# Embedded_II_MAIN_BOARD.net
KiCad netlist of a schematic drawn in EAGLE
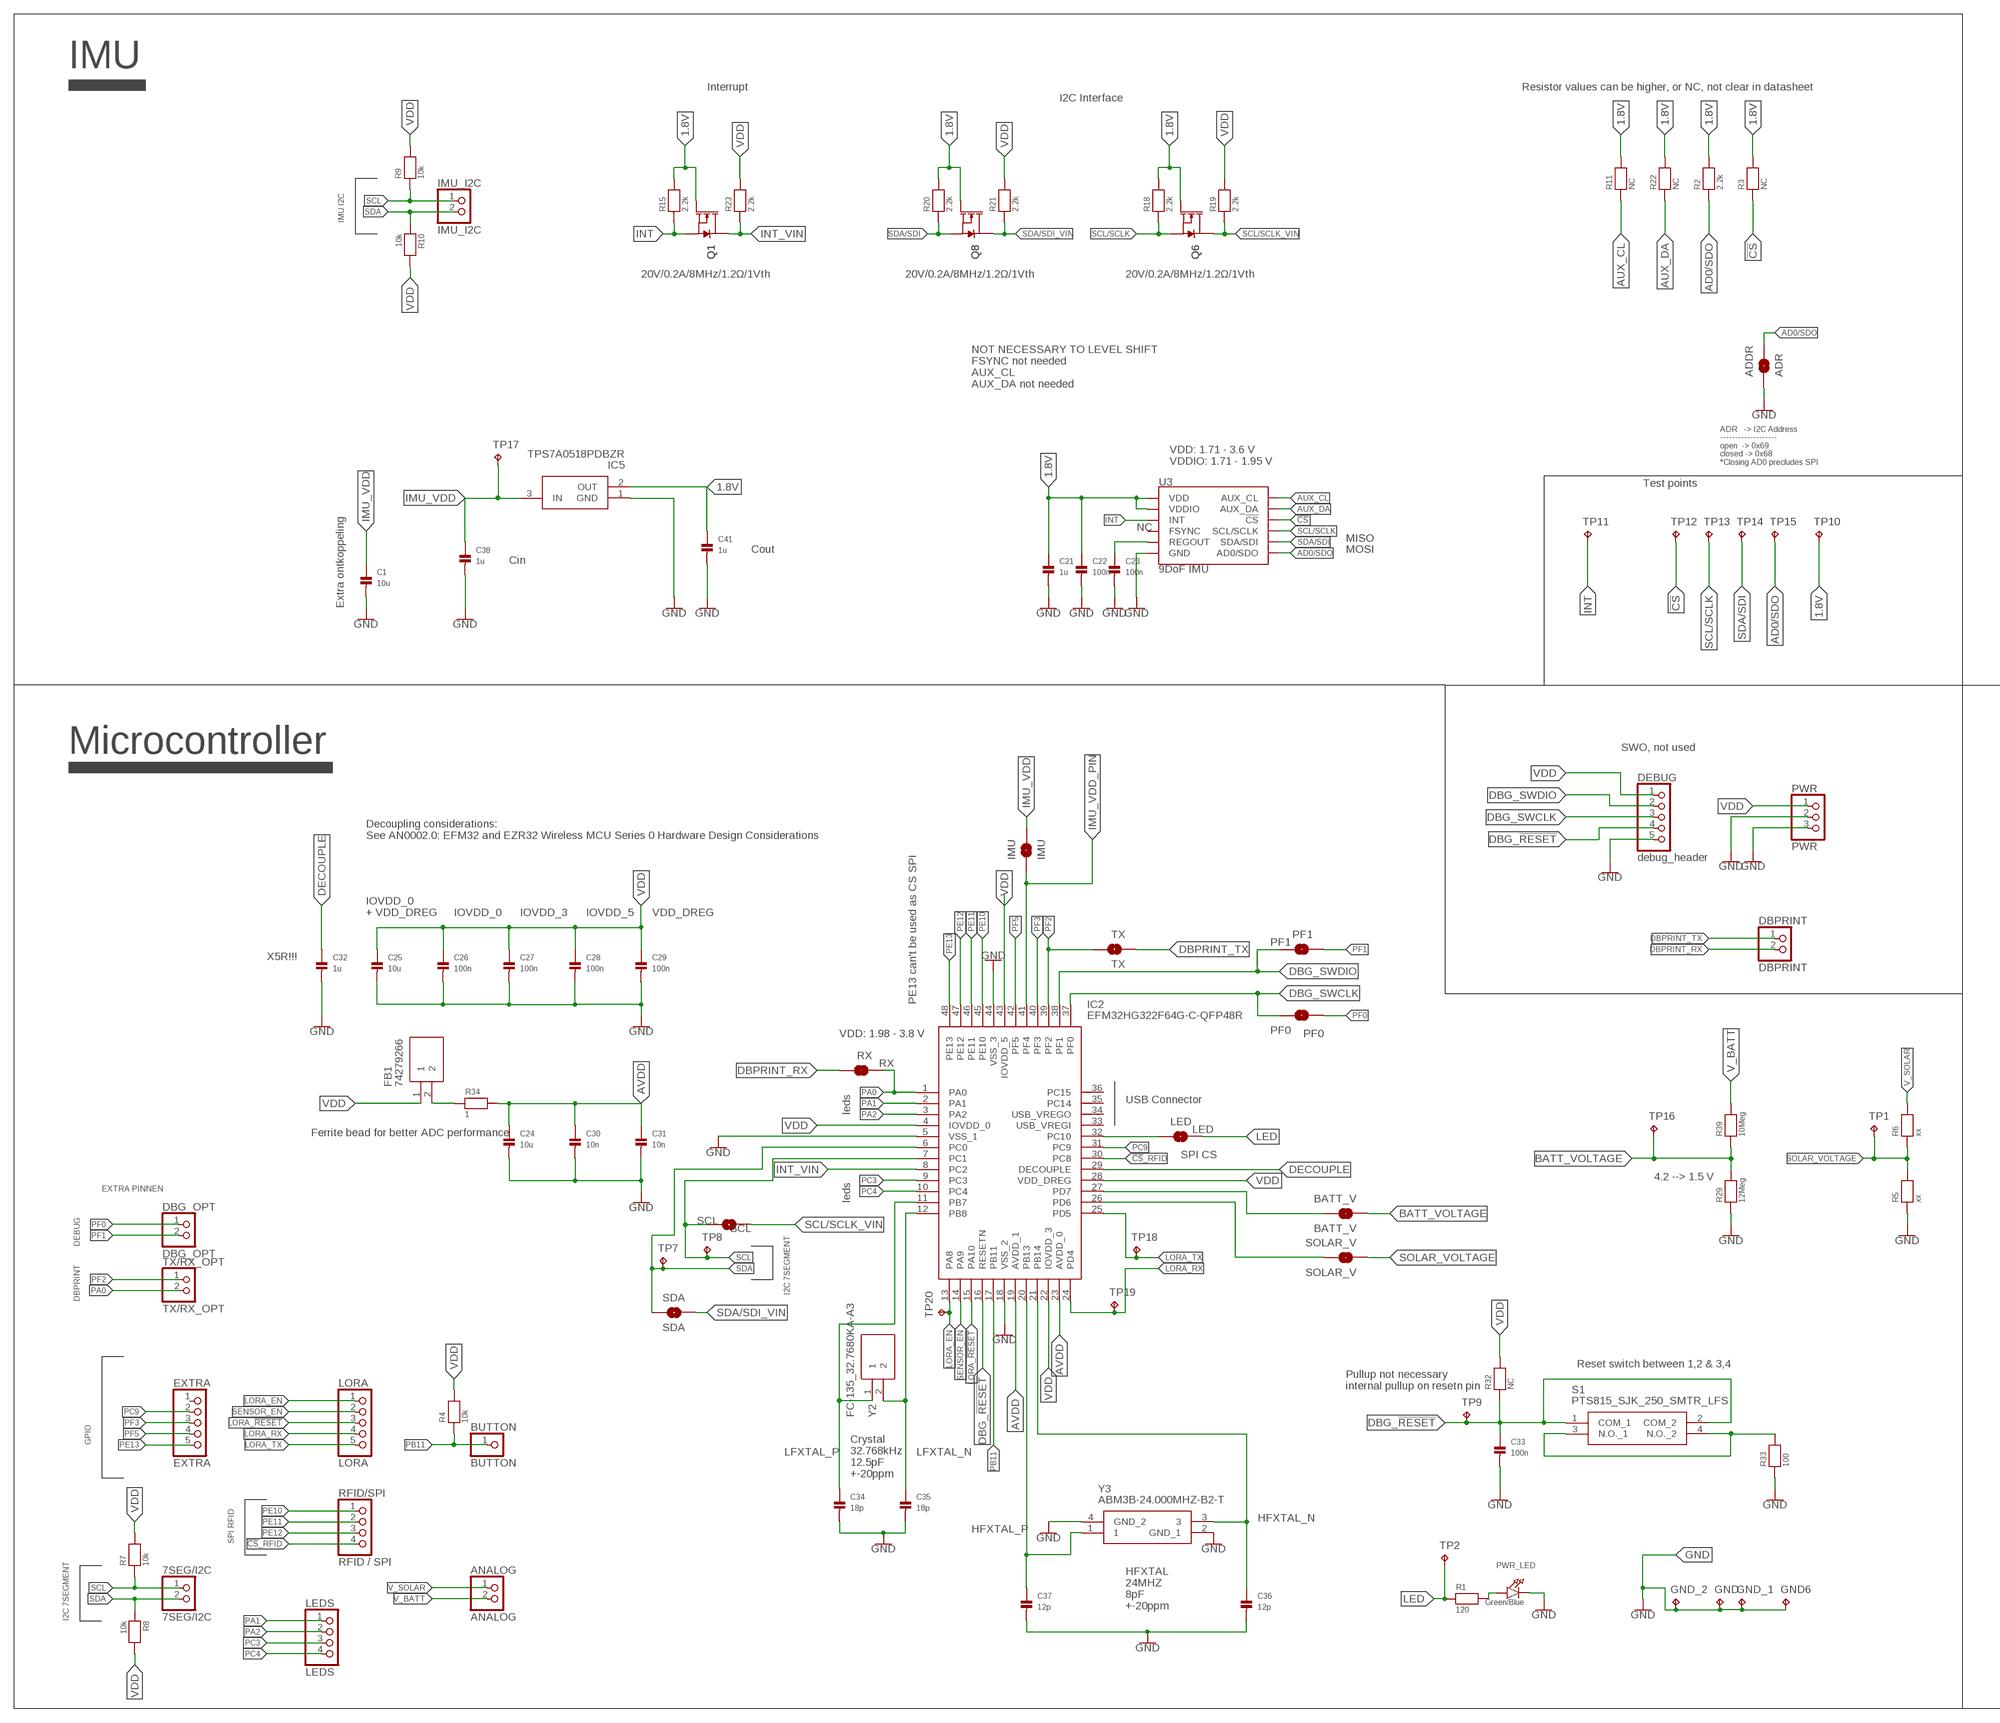
[diagram p0: schematic, sheet 1, part 1 of 2]
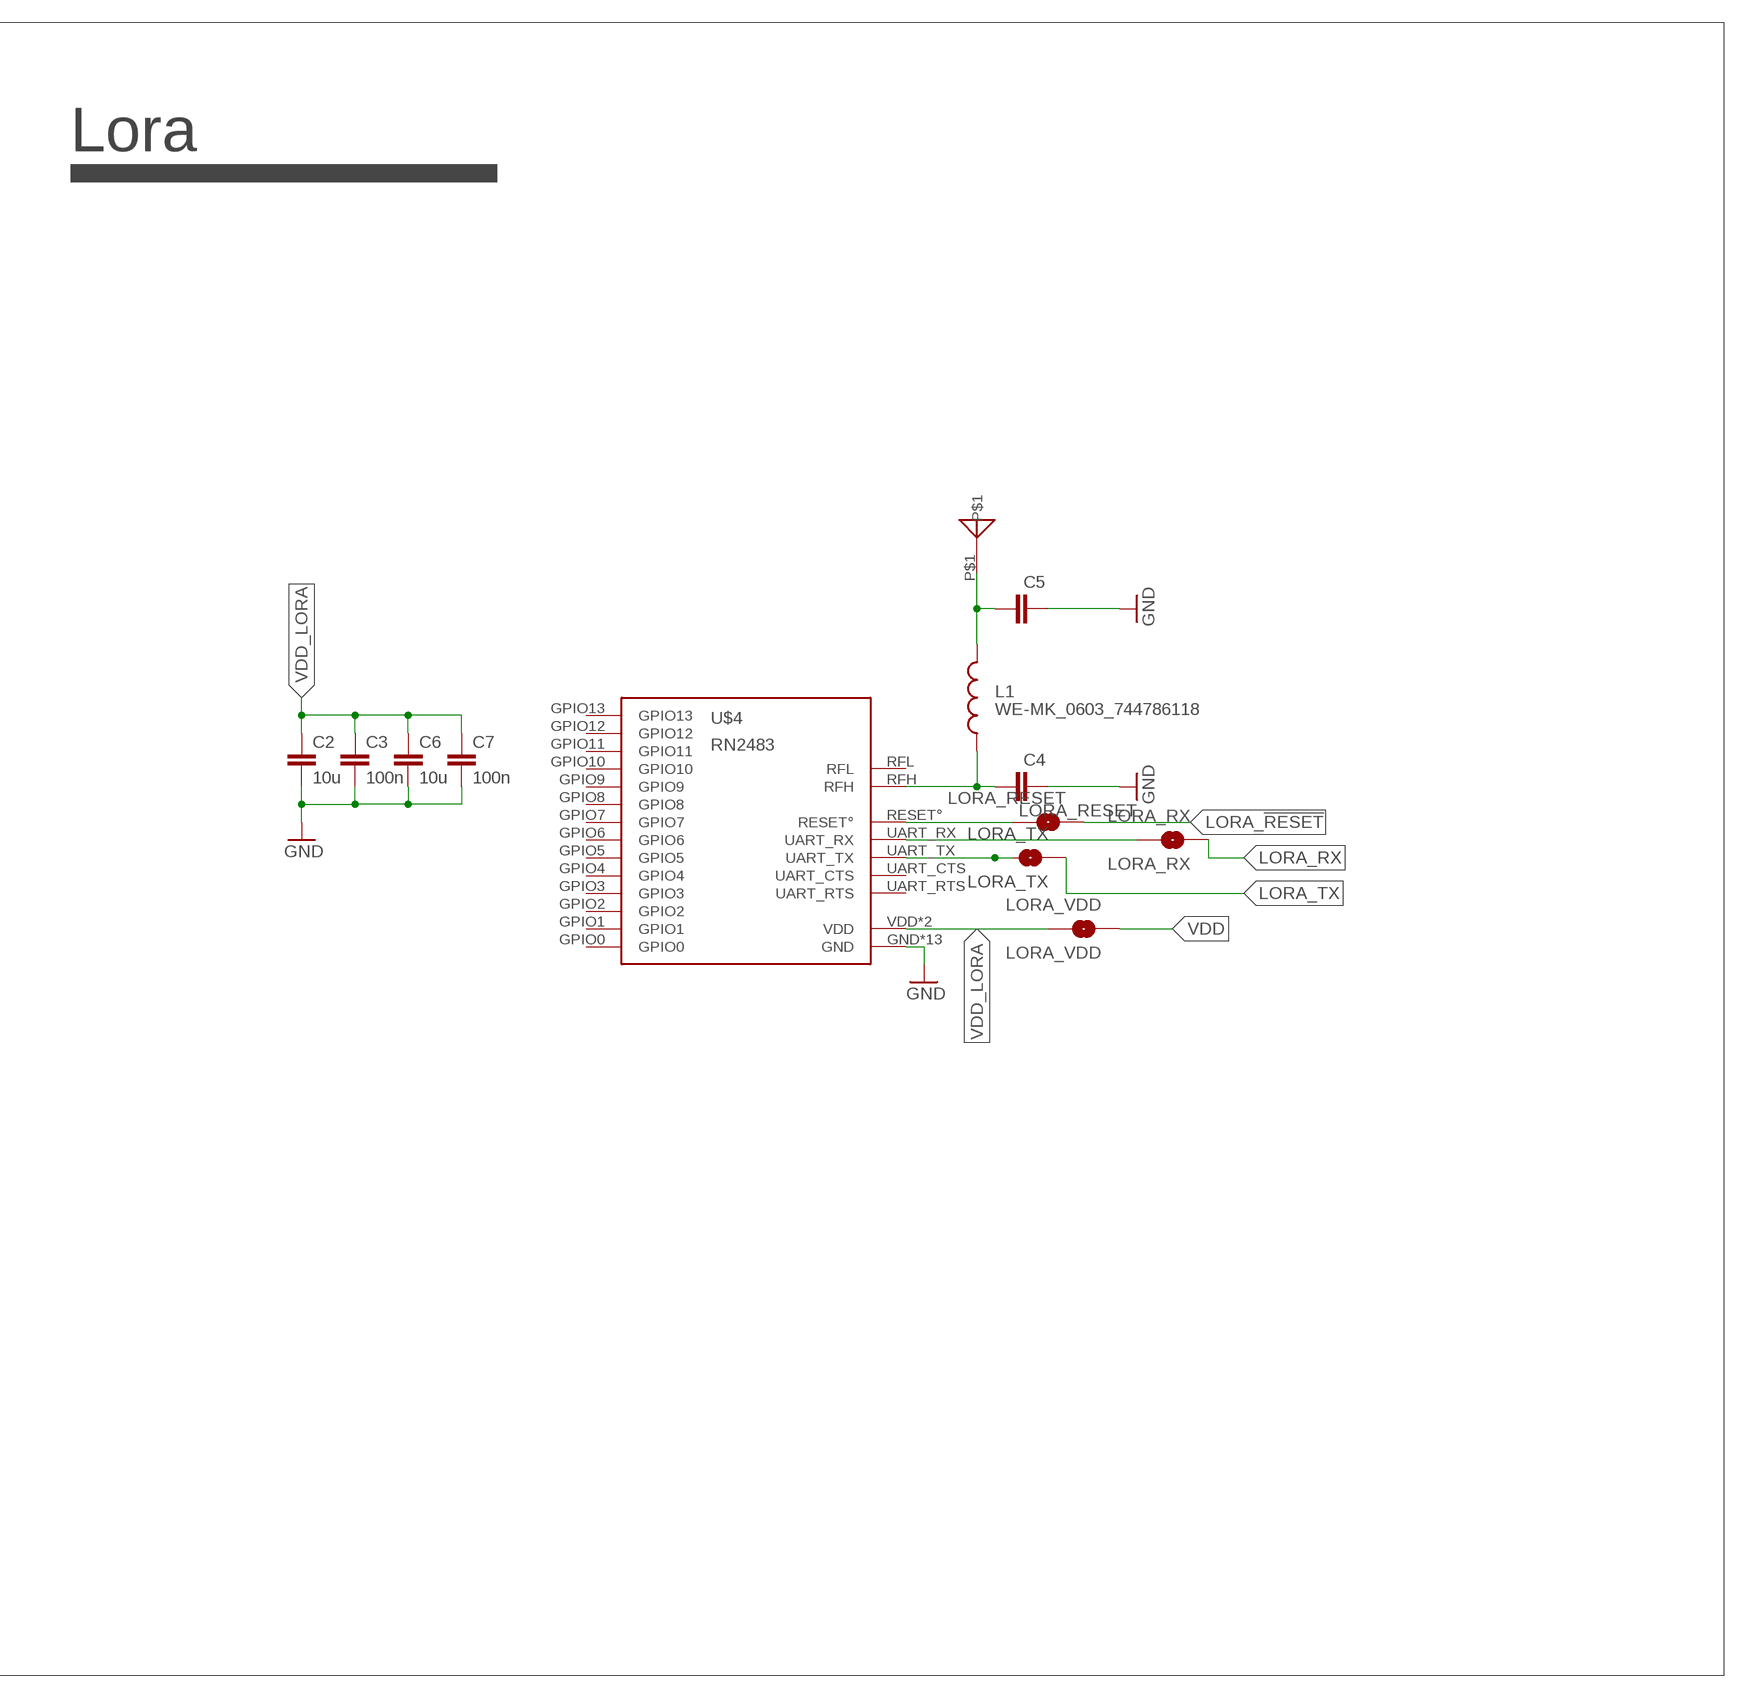
[diagram p1: schematic, sheet 1, part 2 of 2]

(export (version "E")
  (design (tool "Eeschema 10.0.6"))
  (components
    (comp (ref "7SEG/I2C")
      (value "7SEG/I2C")
      (footprint "eagle-import:1X02")
      (libsource (lib "eagle-import") (part "PINHD-1X2"))
    )
    (comp (ref "ADDR")
      (value "ADR")
      (footprint "eagle-import:SMT-JUMPER_2_NO_SILK")
      (libsource (lib "eagle-import") (part "JUMPER-SMT_2_NO_SILK"))
    )
    (comp (ref "ANALOG")
      (value "ANALOG")
      (footprint "eagle-import:1X02")
      (libsource (lib "eagle-import") (part "PINHD-1X2"))
    )
    (comp (ref "BATT_V")
      (value "BATT_V")
      (footprint "eagle-import:SMT-JUMPER_2_NO_SILK")
      (libsource (lib "eagle-import") (part "JUMPER-SMT_2_NO_SILK"))
    )
    (comp (ref "BUTTON")
      (value "BUTTON")
      (footprint "eagle-import:1X01")
      (libsource (lib "eagle-import") (part "PINHD-1X1"))
    )
    (comp (ref "C1")
      (value "10u")
      (footprint "eagle-import:0603")
      (libsource (lib "eagle-import") (part "CAP_CERAMIC0603"))
    )
    (comp (ref "C2")
      (value "10u")
      (footprint "eagle-import:C0805K")
      (libsource (lib "eagle-import") (part "C-EUC0805K"))
    )
    (comp (ref "C3")
      (value "100n")
      (footprint "eagle-import:C0805K")
      (libsource (lib "eagle-import") (part "C-EUC0805K"))
    )
    (comp (ref "C4")
      (value "C-EUC0603K")
      (footprint "eagle-import:C0603K")
      (libsource (lib "eagle-import") (part "C-EUC0603K"))
    )
    (comp (ref "C5")
      (value "C-EUC0603K")
      (footprint "eagle-import:C0603K")
      (libsource (lib "eagle-import") (part "C-EUC0603K"))
    )
    (comp (ref "C6")
      (value "10u")
      (footprint "eagle-import:C0805K")
      (libsource (lib "eagle-import") (part "C-EUC0805K"))
    )
    (comp (ref "C7")
      (value "100n")
      (footprint "eagle-import:C0805K")
      (libsource (lib "eagle-import") (part "C-EUC0805K"))
    )
    (comp (ref "C21")
      (value "1u")
      (footprint "eagle-import:0603")
      (libsource (lib "eagle-import") (part "CAP_CERAMIC0603"))
    )
    (comp (ref "C22")
      (value "100n")
      (footprint "eagle-import:0603")
      (libsource (lib "eagle-import") (part "CAP_CERAMIC0603"))
    )
    (comp (ref "C23")
      (value "100n")
      (footprint "eagle-import:0603")
      (libsource (lib "eagle-import") (part "CAP_CERAMIC0603"))
    )
    (comp (ref "C24")
      (value "10u")
      (footprint "eagle-import:0603")
      (libsource (lib "eagle-import") (part "CAP_CERAMIC0603"))
    )
    (comp (ref "C25")
      (value "10u")
      (footprint "eagle-import:0603")
      (libsource (lib "eagle-import") (part "CAP_CERAMIC0603"))
    )
    (comp (ref "C26")
      (value "100n")
      (footprint "eagle-import:0603")
      (libsource (lib "eagle-import") (part "CAP_CERAMIC0603"))
    )
    (comp (ref "C27")
      (value "100n")
      (footprint "eagle-import:0603")
      (libsource (lib "eagle-import") (part "CAP_CERAMIC0603"))
    )
    (comp (ref "C28")
      (value "100n")
      (footprint "eagle-import:0603")
      (libsource (lib "eagle-import") (part "CAP_CERAMIC0603"))
    )
    (comp (ref "C29")
      (value "100n")
      (footprint "eagle-import:0603")
      (libsource (lib "eagle-import") (part "CAP_CERAMIC0603"))
    )
    (comp (ref "C30")
      (value "10n")
      (footprint "eagle-import:0603")
      (libsource (lib "eagle-import") (part "CAP_CERAMIC0603"))
    )
    (comp (ref "C31")
      (value "10n")
      (footprint "eagle-import:0603")
      (libsource (lib "eagle-import") (part "CAP_CERAMIC0603"))
    )
    (comp (ref "C32")
      (value "1u")
      (footprint "eagle-import:0603")
      (libsource (lib "eagle-import") (part "CAP_CERAMIC0603"))
    )
    (comp (ref "C33")
      (value "100n")
      (footprint "eagle-import:0603")
      (libsource (lib "eagle-import") (part "CAP_CERAMIC0603"))
    )
    (comp (ref "C34")
      (value "18p")
      (footprint "eagle-import:0603")
      (libsource (lib "eagle-import") (part "CAP_CERAMIC0603"))
    )
    (comp (ref "C35")
      (value "18p")
      (footprint "eagle-import:0603")
      (libsource (lib "eagle-import") (part "CAP_CERAMIC0603"))
    )
    (comp (ref "C36")
      (value "12p")
      (footprint "eagle-import:0603")
      (libsource (lib "eagle-import") (part "CAP_CERAMIC0603"))
    )
    (comp (ref "C37")
      (value "12p")
      (footprint "eagle-import:0603")
      (libsource (lib "eagle-import") (part "CAP_CERAMIC0603"))
    )
    (comp (ref "C38")
      (value "1u")
      (footprint "eagle-import:0603")
      (libsource (lib "eagle-import") (part "CAP_CERAMIC0603"))
    )
    (comp (ref "C41")
      (value "1u")
      (footprint "eagle-import:0603")
      (libsource (lib "eagle-import") (part "CAP_CERAMIC0603"))
    )
    (comp (ref "DBG_OPT")
      (value "DBG_OPT")
      (footprint "eagle-import:1X02")
      (libsource (lib "eagle-import") (part "PINHD-1X2"))
    )
    (comp (ref "DBPRINT")
      (value "DBPRINT")
      (footprint "eagle-import:1X02")
      (libsource (lib "eagle-import") (part "PINHD-1X2"))
    )
    (comp (ref "DEBUG")
      (value "debug_header")
      (footprint "eagle-import:1X05")
      (libsource (lib "eagle-import") (part "PINHD-1X5"))
    )
    (comp (ref "EXTRA")
      (value "EXTRA")
      (footprint "eagle-import:1X05")
      (libsource (lib "eagle-import") (part "PINHD-1X5"))
    )
    (comp (ref "FB1")
      (value "74279266")
      (footprint "eagle-import:BEADC1608X100N")
      (fields (field (name "MOUSER_PART_NUMBER") "710-74279266"))
      (libsource (lib "eagle-import") (part "74279266"))
    )
    (comp (ref "GND")
      (value "TPTP20SQ")
      (footprint "eagle-import:TP20SQ")
      (libsource (lib "eagle-import") (part "TPTP20SQ"))
    )
    (comp (ref "GND6")
      (value "TPTP20SQ")
      (footprint "eagle-import:TP20SQ")
      (libsource (lib "eagle-import") (part "TPTP20SQ"))
    )
    (comp (ref "GND_1")
      (value "TPTP20SQ")
      (footprint "eagle-import:TP20SQ")
      (libsource (lib "eagle-import") (part "TPTP20SQ"))
    )
    (comp (ref "GND_2")
      (value "TPTP20SQ")
      (footprint "eagle-import:TP20SQ")
      (libsource (lib "eagle-import") (part "TPTP20SQ"))
    )
    (comp (ref "IC2")
      (value "EFM32HG322F64G-C-QFP48R")
      (footprint "eagle-import:QFP50P900X900X120-48N")
      (fields (field (name "MOUSER_PART_NUMBER") "634-HG322F64GCQFP48R"))
      (libsource (lib "eagle-import") (part "EFM32HG322F64G-C-QFP48R"))
    )
    (comp (ref "IC5")
      (value "TPS7A0518PDBZR")
      (footprint "eagle-import:SOT95P237X112-3N")
      (fields (field (name "MOUSER_PART_NUMBER") "595-TPS7A0518PDBZR"))
      (libsource (lib "eagle-import") (part "TPS7A0518PDBZR"))
    )
    (comp (ref "IMU")
      (value "IMU")
      (footprint "eagle-import:SMT-JUMPER_2_NO_SILK")
      (libsource (lib "eagle-import") (part "JUMPER-SMT_2_NO_SILK"))
    )
    (comp (ref "IMU_I2C")
      (value "IMU_I2C")
      (footprint "eagle-import:1X02")
      (libsource (lib "eagle-import") (part "PINHD-1X2"))
    )
    (comp (ref "L1")
      (value "WE-MK_0603_744786118")
      (footprint "eagle-import:WE-MK_0603")
      (libsource (lib "eagle-import") (part "WE-MK_0603_744786118"))
    )
    (comp (ref "LED")
      (value "LED")
      (footprint "eagle-import:SMT-JUMPER_2_NO_SILK")
      (libsource (lib "eagle-import") (part "JUMPER-SMT_2_NO_SILK"))
    )
    (comp (ref "LEDS")
      (value "LEDS")
      (footprint "eagle-import:1X04")
      (libsource (lib "eagle-import") (part "PINHD-1X4"))
    )
    (comp (ref "LORA")
      (value "LORA")
      (footprint "eagle-import:1X05")
      (libsource (lib "eagle-import") (part "PINHD-1X5"))
    )
    (comp (ref "LORA_RESET")
      (value "LORA_RESET")
      (footprint "eagle-import:SMT-JUMPER_2_NO_SILK")
      (libsource (lib "eagle-import") (part "JUMPER-SMT_2_NO_SILK"))
    )
    (comp (ref "LORA_RX")
      (value "LORA_RX")
      (footprint "eagle-import:SMT-JUMPER_2_NO_SILK")
      (libsource (lib "eagle-import") (part "JUMPER-SMT_2_NO_SILK"))
    )
    (comp (ref "LORA_TX")
      (value "LORA_TX")
      (footprint "eagle-import:SMT-JUMPER_2_NO_SILK")
      (libsource (lib "eagle-import") (part "JUMPER-SMT_2_NO_SILK"))
    )
    (comp (ref "LORA_VDD")
      (value "LORA_VDD")
      (footprint "eagle-import:SMT-JUMPER_2_NO_SILK")
      (libsource (lib "eagle-import") (part "JUMPER-SMT_2_NO_SILK"))
    )
    (comp (ref "PF0")
      (value "PF0")
      (footprint "eagle-import:SMT-JUMPER_2_NO_SILK")
      (libsource (lib "eagle-import") (part "JUMPER-SMT_2_NO_SILK"))
    )
    (comp (ref "PF1")
      (value "PF1")
      (footprint "eagle-import:SMT-JUMPER_2_NO_SILK")
      (libsource (lib "eagle-import") (part "JUMPER-SMT_2_NO_SILK"))
    )
    (comp (ref "PWR")
      (value "PWR")
      (footprint "eagle-import:1X03")
      (libsource (lib "eagle-import") (part "PINHD-1X3"))
    )
    (comp (ref "PWR_LED")
      (value "Green/Blue")
      (footprint "eagle-import:CHIPLED_0805")
      (libsource (lib "eagle-import") (part "LED0805"))
    )
    (comp (ref "Q1")
      (value "20V/0.2A/8MHz/1.2Ω/1Vth")
      (footprint "eagle-import:SOT-416FL")
      (libsource (lib "eagle-import") (part "MOSFET-NCH-RE1C002UN"))
    )
    (comp (ref "Q6")
      (value "20V/0.2A/8MHz/1.2Ω/1Vth")
      (footprint "eagle-import:SOT-416FL")
      (libsource (lib "eagle-import") (part "MOSFET-NCH-RE1C002UN"))
    )
    (comp (ref "Q8")
      (value "20V/0.2A/8MHz/1.2Ω/1Vth")
      (footprint "eagle-import:SOT-416FL")
      (libsource (lib "eagle-import") (part "MOSFET-NCH-RE1C002UN"))
    )
    (comp (ref "R1")
      (value "120")
      (footprint "eagle-import:0603")
      (libsource (lib "eagle-import") (part "RESISTOR0603"))
    )
    (comp (ref "R2")
      (value "2.2k")
      (footprint "eagle-import:0603")
      (libsource (lib "eagle-import") (part "RESISTOR0603"))
    )
    (comp (ref "R3")
      (value "NC")
      (footprint "eagle-import:0603")
      (libsource (lib "eagle-import") (part "RESISTOR0603"))
    )
    (comp (ref "R4")
      (value "10k")
      (footprint "eagle-import:0603")
      (libsource (lib "eagle-import") (part "RESISTOR0603"))
    )
    (comp (ref "R5")
      (value "xx")
      (footprint "eagle-import:0603")
      (libsource (lib "eagle-import") (part "RESISTOR0603"))
    )
    (comp (ref "R6")
      (value "xx")
      (footprint "eagle-import:0603")
      (libsource (lib "eagle-import") (part "RESISTOR0603"))
    )
    (comp (ref "R7")
      (value "10k")
      (footprint "eagle-import:0603")
      (libsource (lib "eagle-import") (part "RESISTOR0603"))
    )
    (comp (ref "R8")
      (value "10k")
      (footprint "eagle-import:0603")
      (libsource (lib "eagle-import") (part "RESISTOR0603"))
    )
    (comp (ref "R9")
      (value "10k")
      (footprint "eagle-import:0603")
      (libsource (lib "eagle-import") (part "RESISTOR0603"))
    )
    (comp (ref "R10")
      (value "10k")
      (footprint "eagle-import:0603")
      (libsource (lib "eagle-import") (part "RESISTOR0603"))
    )
    (comp (ref "R11")
      (value "NC")
      (footprint "eagle-import:0603")
      (libsource (lib "eagle-import") (part "RESISTOR0603"))
    )
    (comp (ref "R15")
      (value "2.2k")
      (footprint "eagle-import:0603")
      (libsource (lib "eagle-import") (part "RESISTOR0603"))
    )
    (comp (ref "R18")
      (value "2.2k")
      (footprint "eagle-import:0603")
      (libsource (lib "eagle-import") (part "RESISTOR0603"))
    )
    (comp (ref "R19")
      (value "2.2k")
      (footprint "eagle-import:0603")
      (libsource (lib "eagle-import") (part "RESISTOR0603"))
    )
    (comp (ref "R20")
      (value "2.2k")
      (footprint "eagle-import:0603")
      (libsource (lib "eagle-import") (part "RESISTOR0603"))
    )
    (comp (ref "R21")
      (value "2.2k")
      (footprint "eagle-import:0603")
      (libsource (lib "eagle-import") (part "RESISTOR0603"))
    )
    (comp (ref "R22")
      (value "NC")
      (footprint "eagle-import:0603")
      (libsource (lib "eagle-import") (part "RESISTOR0603"))
    )
    (comp (ref "R23")
      (value "2.2k")
      (footprint "eagle-import:0603")
      (libsource (lib "eagle-import") (part "RESISTOR0603"))
    )
    (comp (ref "R29")
      (value "12Meg")
      (footprint "eagle-import:0603")
      (libsource (lib "eagle-import") (part "RESISTOR0603"))
    )
    (comp (ref "R32")
      (value "NC")
      (footprint "eagle-import:0603")
      (libsource (lib "eagle-import") (part "RESISTOR0603"))
    )
    (comp (ref "R33")
      (value "100")
      (footprint "eagle-import:0603")
      (libsource (lib "eagle-import") (part "RESISTOR0603"))
    )
    (comp (ref "R34")
      (value "1")
      (footprint "eagle-import:0603")
      (libsource (lib "eagle-import") (part "RESISTOR0603"))
    )
    (comp (ref "R39")
      (value "10Meg")
      (footprint "eagle-import:0603")
      (libsource (lib "eagle-import") (part "RESISTOR0603"))
    )
    (comp (ref "RFID/SPI")
      (value "RFID / SPI")
      (footprint "eagle-import:1X04")
      (libsource (lib "eagle-import") (part "PINHD-1X4"))
    )
    (comp (ref "RX")
      (value "RX")
      (footprint "eagle-import:SMT-JUMPER_2_NO_SILK")
      (libsource (lib "eagle-import") (part "JUMPER-SMT_2_NO_SILK"))
    )
    (comp (ref "S1")
      (value "PTS815_SJK_250_SMTR_LFS")
      (footprint "eagle-import:PTS815SJK250SMTRLFS")
      (fields
        (field (name "MANUFACTURER_PART_NUMBER") "PTS815 SJK 250 SMTR LFS")
        (field (name "MOUSER_PART_NUMBER") "611-PTS815SJK250SMTR")
      )
      (libsource (lib "eagle-import") (part "PTS815_SJK_250_SMTR_LFS"))
    )
    (comp (ref "SCL")
      (value "SCL")
      (footprint "eagle-import:SMT-JUMPER_2_NO_SILK")
      (libsource (lib "eagle-import") (part "JUMPER-SMT_2_NO_SILK"))
    )
    (comp (ref "SDA")
      (value "SDA")
      (footprint "eagle-import:SMT-JUMPER_2_NO_SILK")
      (libsource (lib "eagle-import") (part "JUMPER-SMT_2_NO_SILK"))
    )
    (comp (ref "SOLAR_V")
      (value "SOLAR_V")
      (footprint "eagle-import:SMT-JUMPER_2_NO_SILK")
      (libsource (lib "eagle-import") (part "JUMPER-SMT_2_NO_SILK"))
    )
    (comp (ref "TP1")
      (value "TPTP10R")
      (footprint "eagle-import:TP10R")
      (libsource (lib "eagle-import") (part "TPTP10R"))
    )
    (comp (ref "TP2")
      (value "TPTP10R")
      (footprint "eagle-import:TP10R")
      (libsource (lib "eagle-import") (part "TPTP10R"))
    )
    (comp (ref "TP7")
      (value "TPTP10R")
      (footprint "eagle-import:TP10R")
      (libsource (lib "eagle-import") (part "TPTP10R"))
    )
    (comp (ref "TP8")
      (value "TPTP10R")
      (footprint "eagle-import:TP10R")
      (libsource (lib "eagle-import") (part "TPTP10R"))
    )
    (comp (ref "TP9")
      (value "TPTP10R")
      (footprint "eagle-import:TP10R")
      (libsource (lib "eagle-import") (part "TPTP10R"))
    )
    (comp (ref "TP10")
      (value "TPTP10R")
      (footprint "eagle-import:TP10R")
      (libsource (lib "eagle-import") (part "TPTP10R"))
    )
    (comp (ref "TP11")
      (value "TPTP10R")
      (footprint "eagle-import:TP10R")
      (libsource (lib "eagle-import") (part "TPTP10R"))
    )
    (comp (ref "TP12")
      (value "TPTP10R")
      (footprint "eagle-import:TP10R")
      (libsource (lib "eagle-import") (part "TPTP10R"))
    )
    (comp (ref "TP13")
      (value "TPTP10R")
      (footprint "eagle-import:TP10R")
      (libsource (lib "eagle-import") (part "TPTP10R"))
    )
    (comp (ref "TP14")
      (value "TPTP10R")
      (footprint "eagle-import:TP10R")
      (libsource (lib "eagle-import") (part "TPTP10R"))
    )
    (comp (ref "TP15")
      (value "TPTP10R")
      (footprint "eagle-import:TP10R")
      (libsource (lib "eagle-import") (part "TPTP10R"))
    )
    (comp (ref "TP16")
      (value "TPTP10R")
      (footprint "eagle-import:TP10R")
      (libsource (lib "eagle-import") (part "TPTP10R"))
    )
    (comp (ref "TP17")
      (value "TPTP10R")
      (footprint "eagle-import:TP10R")
      (libsource (lib "eagle-import") (part "TPTP10R"))
    )
    (comp (ref "TP18")
      (value "TPTP10R")
      (footprint "eagle-import:TP10R")
      (libsource (lib "eagle-import") (part "TPTP10R"))
    )
    (comp (ref "TP19")
      (value "TPTP10R")
      (footprint "eagle-import:TP10R")
      (libsource (lib "eagle-import") (part "TPTP10R"))
    )
    (comp (ref "TP20")
      (value "TPTP10R")
      (footprint "eagle-import:TP10R")
      (libsource (lib "eagle-import") (part "TPTP10R"))
    )
    (comp (ref "TX")
      (value "TX")
      (footprint "eagle-import:SMT-JUMPER_2_NO_SILK")
      (libsource (lib "eagle-import") (part "JUMPER-SMT_2_NO_SILK"))
    )
    (comp (ref "TX/RX_OPT")
      (value "TX/RX_OPT")
      (footprint "eagle-import:1X02")
      (libsource (lib "eagle-import") (part "PINHD-1X2"))
    )
    (comp (ref "U$2")
      (value "ANTENNA868")
      (footprint "eagle-import:CERAMIC-ANTENNA")
      (libsource (lib "eagle-import") (part "ANTENNA868"))
    )
    (comp (ref "U$4")
      (value "RN2483")
      (footprint "eagle-import:RN2483")
      (libsource (lib "eagle-import") (part "RN2483"))
    )
    (comp (ref "U3")
      (value "9DoF IMU")
      (footprint "eagle-import:SPARKFUN-SENSORS_QFN24-3X3")
      (libsource (lib "eagle-import") (part "SPARKFUN-SENSORS_ICM-20948"))
    )
    (comp (ref "Y2")
      (value "FC-135_32.7680KA-A3")
      (footprint "eagle-import:FC135327680KAAG0")
      (fields
        (field (name "MANUFACTURER_PART_NUMBER") "FC-135 32.7680KA-A3")
        (field (name "MOUSER_PART_NUMBER") "732-FC135-32.76KAA3")
      )
      (libsource (lib "eagle-import") (part "FC-135_32.7680KA-A3"))
    )
    (comp (ref "Y3")
      (value "ABM3B-24.000MHZ-B2-T")
      (footprint "eagle-import:ABM3B8000MHZ101UT")
      (fields (field (name "MOUSER_PART_NUMBER") "815-ABM3B-24-B2"))
      (libsource (lib "eagle-import") (part "ABM3B-24.000MHZ-B2-T"))
    )
  )
  (nets
    (net (code "1") (name "/DBG_~{RESET}") (class "Default")
      (node (ref "C33") (pin "1") (pinfunction "P$1_1") (pintype "passive"))
      (node (ref "DEBUG") (pin "4") (pinfunction "4_4") (pintype "passive"))
      (node (ref "IC2") (pin "16") (pinfunction "RESETN_16") (pintype "bidirectional"))
      (node (ref "R32") (pin "1") (pinfunction "1_1") (pintype "passive"))
      (node (ref "S1") (pin "1") (pinfunction "COM_1_1") (pintype "bidirectional"))
      (node (ref "S1") (pin "2") (pinfunction "COM_2_2") (pintype "bidirectional"))
      (node (ref "TP9") (pin "TP") (pinfunction "TP_TP") (pintype "input"))
    )
    (net (code "2") (name "/LORA_~{RESET}") (class "Default")
      (node (ref "IC2") (pin "15") (pinfunction "PA10_15") (pintype "bidirectional"))
      (node (ref "LORA") (pin "3") (pinfunction "3_3") (pintype "passive"))
      (node (ref "LORA_RESET") (pin "1") (pinfunction "1_1") (pintype "passive"))
    )
    (net (code "3") (name "/~{CS}") (class "Default")
      (node (ref "R3") (pin "1") (pinfunction "1_1") (pintype "passive"))
      (node (ref "TP12") (pin "TP") (pinfunction "TP_TP") (pintype "input"))
      (node (ref "U3") (pin "22") (pinfunction "~{CS}_22") (pintype "bidirectional"))
    )
    (net (code "4") (name "/~{CS}_RFID") (class "Default")
      (node (ref "IC2") (pin "30") (pinfunction "PC8_30") (pintype "bidirectional"))
      (node (ref "RFID/SPI") (pin "4") (pinfunction "4_4") (pintype "passive"))
    )
    (net (code "5") (name "1.8V") (class "Default")
      (node (ref "C21") (pin "1") (pinfunction "P$1_1") (pintype "passive"))
      (node (ref "C22") (pin "1") (pinfunction "P$1_1") (pintype "passive"))
      (node (ref "C41") (pin "1") (pinfunction "P$1_1") (pintype "passive"))
      (node (ref "IC5") (pin "2") (pinfunction "OUT_2") (pintype "bidirectional"))
      (node (ref "Q1") (pin "1") (pinfunction "G_1") (pintype "bidirectional"))
      (node (ref "Q6") (pin "1") (pinfunction "G_1") (pintype "bidirectional"))
      (node (ref "Q8") (pin "1") (pinfunction "G_1") (pintype "bidirectional"))
      (node (ref "R11") (pin "2") (pinfunction "2_2") (pintype "passive"))
      (node (ref "R15") (pin "2") (pinfunction "2_2") (pintype "passive"))
      (node (ref "R18") (pin "2") (pinfunction "2_2") (pintype "passive"))
      (node (ref "R2") (pin "2") (pinfunction "2_2") (pintype "passive"))
      (node (ref "R20") (pin "2") (pinfunction "2_2") (pintype "passive"))
      (node (ref "R22") (pin "2") (pinfunction "2_2") (pintype "passive"))
      (node (ref "R3") (pin "2") (pinfunction "2_2") (pintype "passive"))
      (node (ref "TP10") (pin "TP") (pinfunction "TP_TP") (pintype "input"))
      (node (ref "U3") (pin "13") (pinfunction "VDD_13") (pintype "bidirectional"))
      (node (ref "U3") (pin "8") (pinfunction "VDDIO_8") (pintype "bidirectional"))
    )
    (net (code "6") (name "AD0{slash}SDO") (class "Default")
      (node (ref "ADDR") (pin "2") (pinfunction "2_2") (pintype "passive"))
      (node (ref "R2") (pin "1") (pinfunction "1_1") (pintype "passive"))
      (node (ref "TP15") (pin "TP") (pinfunction "TP_TP") (pintype "input"))
      (node (ref "U3") (pin "9") (pinfunction "AD0/SDO_9") (pintype "bidirectional"))
    )
    (net (code "7") (name "AUX_CL") (class "Default")
      (node (ref "R11") (pin "1") (pinfunction "1_1") (pintype "passive"))
      (node (ref "U3") (pin "7") (pinfunction "AUX_CL_7") (pintype "bidirectional"))
    )
    (net (code "8") (name "AUX_DA") (class "Default")
      (node (ref "R22") (pin "1") (pinfunction "1_1") (pintype "passive"))
      (node (ref "U3") (pin "21") (pinfunction "AUX_DA_21") (pintype "bidirectional"))
    )
    (net (code "9") (name "AVDD") (class "Default")
      (node (ref "C24") (pin "1") (pinfunction "P$1_1") (pintype "passive"))
      (node (ref "C30") (pin "1") (pinfunction "P$1_1") (pintype "passive"))
      (node (ref "C31") (pin "1") (pinfunction "P$1_1") (pintype "passive"))
      (node (ref "IC2") (pin "19") (pinfunction "AVDD_1_19") (pintype "bidirectional"))
      (node (ref "IC2") (pin "23") (pinfunction "AVDD_0_23") (pintype "bidirectional"))
      (node (ref "R34") (pin "2") (pinfunction "2_2") (pintype "passive"))
    )
    (net (code "10") (name "BATT_VOLTAGE") (class "Default")
      (node (ref "BATT_V") (pin "1") (pinfunction "1_1") (pintype "passive"))
      (node (ref "R29") (pin "2") (pinfunction "2_2") (pintype "passive"))
      (node (ref "R39") (pin "1") (pinfunction "1_1") (pintype "passive"))
      (node (ref "TP16") (pin "TP") (pinfunction "TP_TP") (pintype "input"))
    )
    (net (code "11") (name "DBG_SWCLK") (class "Default")
      (node (ref "DEBUG") (pin "3") (pinfunction "3_3") (pintype "passive"))
      (node (ref "IC2") (pin "37") (pinfunction "PF0_37") (pintype "bidirectional"))
      (node (ref "PF0") (pin "2") (pinfunction "2_2") (pintype "passive"))
    )
    (net (code "12") (name "DBG_SWDIO") (class "Default")
      (node (ref "DEBUG") (pin "2") (pinfunction "2_2") (pintype "passive"))
      (node (ref "IC2") (pin "38") (pinfunction "PF1_38") (pintype "bidirectional"))
      (node (ref "PF1") (pin "2") (pinfunction "2_2") (pintype "passive"))
    )
    (net (code "13") (name "DBPRINT_RX") (class "Default")
      (node (ref "DBPRINT") (pin "2") (pinfunction "2_2") (pintype "passive"))
      (node (ref "RX") (pin "2") (pinfunction "2_2") (pintype "passive"))
    )
    (net (code "14") (name "DBPRINT_TX") (class "Default")
      (node (ref "DBPRINT") (pin "1") (pinfunction "1_1") (pintype "passive"))
      (node (ref "TX") (pin "1") (pinfunction "1_1") (pintype "passive"))
    )
    (net (code "15") (name "DECOUPLE") (class "Default")
      (node (ref "C32") (pin "1") (pinfunction "P$1_1") (pintype "passive"))
      (node (ref "IC2") (pin "29") (pinfunction "DECOUPLE_29") (pintype "bidirectional"))
    )
    (net (code "16") (name "GND") (class "Default")
      (node (ref "ADDR") (pin "1") (pinfunction "1_1") (pintype "passive"))
      (node (ref "C1") (pin "2") (pinfunction "P$2_2") (pintype "passive"))
      (node (ref "C2") (pin "2") (pinfunction "2_2") (pintype "passive"))
      (node (ref "C21") (pin "2") (pinfunction "P$2_2") (pintype "passive"))
      (node (ref "C22") (pin "2") (pinfunction "P$2_2") (pintype "passive"))
      (node (ref "C23") (pin "2") (pinfunction "P$2_2") (pintype "passive"))
      (node (ref "C24") (pin "2") (pinfunction "P$2_2") (pintype "passive"))
      (node (ref "C25") (pin "2") (pinfunction "P$2_2") (pintype "passive"))
      (node (ref "C26") (pin "2") (pinfunction "P$2_2") (pintype "passive"))
      (node (ref "C27") (pin "2") (pinfunction "P$2_2") (pintype "passive"))
      (node (ref "C28") (pin "2") (pinfunction "P$2_2") (pintype "passive"))
      (node (ref "C29") (pin "2") (pinfunction "P$2_2") (pintype "passive"))
      (node (ref "C3") (pin "2") (pinfunction "2_2") (pintype "passive"))
      (node (ref "C30") (pin "2") (pinfunction "P$2_2") (pintype "passive"))
      (node (ref "C31") (pin "2") (pinfunction "P$2_2") (pintype "passive"))
      (node (ref "C32") (pin "2") (pinfunction "P$2_2") (pintype "passive"))
      (node (ref "C33") (pin "2") (pinfunction "P$2_2") (pintype "passive"))
      (node (ref "C34") (pin "2") (pinfunction "P$2_2") (pintype "passive"))
      (node (ref "C35") (pin "2") (pinfunction "P$2_2") (pintype "passive"))
      (node (ref "C36") (pin "2") (pinfunction "P$2_2") (pintype "passive"))
      (node (ref "C37") (pin "2") (pinfunction "P$2_2") (pintype "passive"))
      (node (ref "C38") (pin "2") (pinfunction "P$2_2") (pintype "passive"))
      (node (ref "C4") (pin "1") (pinfunction "1_1") (pintype "passive"))
      (node (ref "C41") (pin "2") (pinfunction "P$2_2") (pintype "passive"))
      (node (ref "C5") (pin "1") (pinfunction "1_1") (pintype "passive"))
      (node (ref "C6") (pin "2") (pinfunction "2_2") (pintype "passive"))
      (node (ref "C7") (pin "2") (pinfunction "2_2") (pintype "passive"))
      (node (ref "DEBUG") (pin "5") (pinfunction "5_5") (pintype "passive"))
      (node (ref "GND") (pin "TP") (pinfunction "TP_TP") (pintype "input"))
      (node (ref "GND6") (pin "TP") (pinfunction "TP_TP") (pintype "input"))
      (node (ref "GND_1") (pin "TP") (pinfunction "TP_TP") (pintype "input"))
      (node (ref "GND_2") (pin "TP") (pinfunction "TP_TP") (pintype "input"))
      (node (ref "IC2") (pin "18") (pinfunction "VSS_2_18") (pintype "bidirectional"))
      (node (ref "IC2") (pin "44") (pinfunction "VSS_3_44") (pintype "bidirectional"))
      (node (ref "IC2") (pin "5") (pinfunction "VSS_1_5") (pintype "bidirectional"))
      (node (ref "IC5") (pin "1") (pinfunction "GND_1") (pintype "bidirectional"))
      (node (ref "PWR") (pin "2") (pinfunction "2_2") (pintype "passive"))
      (node (ref "PWR") (pin "3") (pinfunction "3_3") (pintype "passive"))
      (node (ref "PWR_LED") (pin "C") (pinfunction "C_C") (pintype "passive"))
      (node (ref "R29") (pin "1") (pinfunction "1_1") (pintype "passive"))
      (node (ref "R33") (pin "1") (pinfunction "1_1") (pintype "passive"))
      (node (ref "R5") (pin "1") (pinfunction "1_1") (pintype "passive"))
      (node (ref "U$4") (pin "GND") (pinfunction "GND_GND") (pintype "bidirectional"))
      (node (ref "U$4") (pin "GND1") (pinfunction "GND_GND1") (pintype "bidirectional"))
      (node (ref "U$4") (pin "GND10") (pinfunction "GND_GND10") (pintype "bidirectional"))
      (node (ref "U$4") (pin "GND11") (pinfunction "GND_GND11") (pintype "bidirectional"))
      (node (ref "U$4") (pin "GND12") (pinfunction "GND_GND12") (pintype "bidirectional"))
      (node (ref "U$4") (pin "GND2") (pinfunction "GND_GND2") (pintype "bidirectional"))
      (node (ref "U$4") (pin "GND3") (pinfunction "GND_GND3") (pintype "bidirectional"))
      (node (ref "U$4") (pin "GND4") (pinfunction "GND_GND4") (pintype "bidirectional"))
      (node (ref "U$4") (pin "GND5") (pinfunction "GND_GND5") (pintype "bidirectional"))
      (node (ref "U$4") (pin "GND6") (pinfunction "GND_GND6") (pintype "bidirectional"))
      (node (ref "U$4") (pin "GND7") (pinfunction "GND_GND7") (pintype "bidirectional"))
      (node (ref "U$4") (pin "GND8") (pinfunction "GND_GND8") (pintype "bidirectional"))
      (node (ref "U$4") (pin "GND9") (pinfunction "GND_GND9") (pintype "bidirectional"))
      (node (ref "U3") (pin "18") (pinfunction "GND_18") (pintype "bidirectional"))
      (node (ref "U3") (pin "20") (pinfunction "GND_20") (pintype "bidirectional"))
      (node (ref "Y3") (pin "2") (pinfunction "GND_1_2") (pintype "bidirectional"))
      (node (ref "Y3") (pin "4") (pinfunction "GND_2_4") (pintype "bidirectional"))
    )
    (net (code "17") (name "IMU_VDD") (class "Default")
      (node (ref "C1") (pin "1") (pinfunction "P$1_1") (pintype "passive"))
      (node (ref "C38") (pin "1") (pinfunction "P$1_1") (pintype "passive"))
      (node (ref "IC5") (pin "3") (pinfunction "IN_3") (pintype "bidirectional"))
      (node (ref "IMU") (pin "1") (pinfunction "1_1") (pintype "passive"))
      (node (ref "TP17") (pin "TP") (pinfunction "TP_TP") (pintype "input"))
    )
    (net (code "18") (name "IMU_VDD_PIN") (class "Default")
      (node (ref "IC2") (pin "41") (pinfunction "PF4_41") (pintype "bidirectional"))
      (node (ref "IMU") (pin "2") (pinfunction "2_2") (pintype "passive"))
    )
    (net (code "19") (name "INT") (class "Default")
      (node (ref "Q1") (pin "2") (pinfunction "S_2") (pintype "bidirectional"))
      (node (ref "R15") (pin "1") (pinfunction "1_1") (pintype "passive"))
      (node (ref "TP11") (pin "TP") (pinfunction "TP_TP") (pintype "input"))
      (node (ref "U3") (pin "12") (pinfunction "INT_12") (pintype "bidirectional"))
    )
    (net (code "20") (name "INT_VIN") (class "Default")
      (node (ref "IC2") (pin "8") (pinfunction "PC2_8") (pintype "bidirectional"))
      (node (ref "Q1") (pin "3") (pinfunction "D_3") (pintype "bidirectional"))
      (node (ref "R23") (pin "1") (pinfunction "1_1") (pintype "passive"))
    )
    (net (code "21") (name "LED") (class "Default")
      (node (ref "LED") (pin "1") (pinfunction "1_1") (pintype "passive"))
      (node (ref "R1") (pin "1") (pinfunction "1_1") (pintype "passive"))
      (node (ref "TP2") (pin "TP") (pinfunction "TP_TP") (pintype "input"))
    )
    (net (code "22") (name "LORA_EN") (class "Default")
      (node (ref "IC2") (pin "13") (pinfunction "PA8_13") (pintype "bidirectional"))
      (node (ref "LORA") (pin "1") (pinfunction "1_1") (pintype "passive"))
      (node (ref "TP20") (pin "TP") (pinfunction "TP_TP") (pintype "input"))
    )
    (net (code "23") (name "LORA_RX") (class "Default")
      (node (ref "IC2") (pin "24") (pinfunction "PD4_24") (pintype "bidirectional"))
      (node (ref "LORA") (pin "4") (pinfunction "4_4") (pintype "passive"))
      (node (ref "LORA_RX") (pin "1") (pinfunction "1_1") (pintype "passive"))
      (node (ref "TP19") (pin "TP") (pinfunction "TP_TP") (pintype "input"))
    )
    (net (code "24") (name "LORA_TX") (class "Default")
      (node (ref "IC2") (pin "25") (pinfunction "PD5_25") (pintype "bidirectional"))
      (node (ref "LORA") (pin "5") (pinfunction "5_5") (pintype "passive"))
      (node (ref "LORA_TX") (pin "1") (pinfunction "1_1") (pintype "passive"))
      (node (ref "TP18") (pin "TP") (pinfunction "TP_TP") (pintype "input"))
    )
    (net (code "25") (name "Net-(C4-Pad2)") (class "Default")
      (node (ref "C4") (pin "2") (pinfunction "2_2") (pintype "passive"))
      (node (ref "L1") (pin "1") (pinfunction "1_1") (pintype "passive"))
      (node (ref "U$4") (pin "RFH") (pinfunction "RFH_RFH") (pintype "bidirectional"))
    )
    (net (code "26") (name "Net-(C5-Pad2)") (class "Default")
      (node (ref "C5") (pin "2") (pinfunction "2_2") (pintype "passive"))
      (node (ref "L1") (pin "2") (pinfunction "2_2") (pintype "passive"))
      (node (ref "U$2") (pin "P$1") (pinfunction "P$1_P$1") (pintype "bidirectional"))
    )
    (net (code "27") (name "Net-(C23-P$1)") (class "Default")
      (node (ref "C23") (pin "1") (pinfunction "P$1_1") (pintype "passive"))
      (node (ref "U3") (pin "10") (pinfunction "REGOUT_10") (pintype "bidirectional"))
    )
    (net (code "28") (name "Net-(C34-P$1)") (class "Default")
      (node (ref "C34") (pin "1") (pinfunction "P$1_1") (pintype "passive"))
      (node (ref "IC2") (pin "11") (pinfunction "PB7_11") (pintype "bidirectional"))
      (node (ref "Y2") (pin "1") (pinfunction "1_1") (pintype "bidirectional"))
    )
    (net (code "29") (name "Net-(C35-P$1)") (class "Default")
      (node (ref "C35") (pin "1") (pinfunction "P$1_1") (pintype "passive"))
      (node (ref "IC2") (pin "12") (pinfunction "PB8_12") (pintype "bidirectional"))
      (node (ref "Y2") (pin "2") (pinfunction "2_2") (pintype "bidirectional"))
    )
    (net (code "30") (name "Net-(C36-P$1)") (class "Default")
      (node (ref "C36") (pin "1") (pinfunction "P$1_1") (pintype "passive"))
      (node (ref "IC2") (pin "21") (pinfunction "PB14_21") (pintype "bidirectional"))
      (node (ref "Y3") (pin "3") (pinfunction "3_3") (pintype "bidirectional"))
    )
    (net (code "31") (name "Net-(C37-P$1)") (class "Default")
      (node (ref "C37") (pin "1") (pinfunction "P$1_1") (pintype "passive"))
      (node (ref "IC2") (pin "20") (pinfunction "PB13_20") (pintype "bidirectional"))
      (node (ref "Y3") (pin "1") (pinfunction "1_1") (pintype "bidirectional"))
    )
    (net (code "32") (name "Net-(FB1-Pad2)") (class "Default")
      (node (ref "FB1") (pin "2") (pinfunction "2_2") (pintype "bidirectional"))
      (node (ref "R34") (pin "1") (pinfunction "1_1") (pintype "passive"))
    )
    (net (code "33") (name "Net-(IC2-PC10)") (class "Default")
      (node (ref "IC2") (pin "32") (pinfunction "PC10_32") (pintype "bidirectional"))
      (node (ref "LED") (pin "2") (pinfunction "2_2") (pintype "passive"))
    )
    (net (code "34") (name "Net-(IC2-PD6)") (class "Default")
      (node (ref "IC2") (pin "26") (pinfunction "PD6_26") (pintype "bidirectional"))
      (node (ref "SOLAR_V") (pin "2") (pinfunction "2_2") (pintype "passive"))
    )
    (net (code "35") (name "Net-(IC2-PD7)") (class "Default")
      (node (ref "BATT_V") (pin "2") (pinfunction "2_2") (pintype "passive"))
      (node (ref "IC2") (pin "27") (pinfunction "PD7_27") (pintype "bidirectional"))
    )
    (net (code "36") (name "Net-(LORA_RESET-Pad2)") (class "Default")
      (node (ref "LORA_RESET") (pin "2") (pinfunction "2_2") (pintype "passive"))
      (node (ref "U$4") (pin "RESET°") (pinfunction "RESET°_RESET°") (pintype "bidirectional"))
    )
    (net (code "37") (name "Net-(LORA_RX-Pad2)") (class "Default")
      (node (ref "LORA_RX") (pin "2") (pinfunction "2_2") (pintype "passive"))
      (node (ref "U$4") (pin "UART_RX") (pinfunction "UART_RX_UART_RX") (pintype "bidirectional"))
    )
    (net (code "38") (name "Net-(LORA_TX-Pad2)") (class "Default")
      (node (ref "LORA_TX") (pin "2") (pinfunction "2_2") (pintype "passive"))
      (node (ref "U$4") (pin "UART_TX") (pinfunction "UART_TX_UART_TX") (pintype "bidirectional"))
    )
    (net (code "39") (name "Net-(PWR_LED-PadA)") (class "Default")
      (node (ref "PWR_LED") (pin "A") (pinfunction "A_A") (pintype "passive"))
      (node (ref "R1") (pin "2") (pinfunction "2_2") (pintype "passive"))
    )
    (net (code "40") (name "Net-(S1-N.O._1)") (class "Default")
      (node (ref "R33") (pin "2") (pinfunction "2_2") (pintype "passive"))
      (node (ref "S1") (pin "3") (pinfunction "N.O._1_3") (pintype "bidirectional"))
      (node (ref "S1") (pin "4") (pinfunction "N.O._2_4") (pintype "bidirectional"))
    )
    (net (code "41") (name "PA0") (class "Default")
      (node (ref "IC2") (pin "1") (pinfunction "PA0_1") (pintype "bidirectional"))
      (node (ref "RX") (pin "1") (pinfunction "1_1") (pintype "passive"))
      (node (ref "TX/RX_OPT") (pin "2") (pinfunction "2_2") (pintype "passive"))
    )
    (net (code "42") (name "PA1") (class "Default")
      (node (ref "IC2") (pin "2") (pinfunction "PA1_2") (pintype "bidirectional"))
      (node (ref "LEDS") (pin "1") (pinfunction "1_1") (pintype "passive"))
    )
    (net (code "43") (name "PA2") (class "Default")
      (node (ref "IC2") (pin "3") (pinfunction "PA2_3") (pintype "bidirectional"))
      (node (ref "LEDS") (pin "2") (pinfunction "2_2") (pintype "passive"))
    )
    (net (code "44") (name "PB11") (class "Default")
      (node (ref "BUTTON") (pin "1") (pinfunction "1_1") (pintype "passive"))
      (node (ref "IC2") (pin "17") (pinfunction "PB11_17") (pintype "bidirectional"))
      (node (ref "R4") (pin "1") (pinfunction "1_1") (pintype "passive"))
    )
    (net (code "45") (name "PC3") (class "Default")
      (node (ref "IC2") (pin "9") (pinfunction "PC3_9") (pintype "bidirectional"))
      (node (ref "LEDS") (pin "3") (pinfunction "3_3") (pintype "passive"))
    )
    (net (code "46") (name "PC4") (class "Default")
      (node (ref "IC2") (pin "10") (pinfunction "PC4_10") (pintype "bidirectional"))
      (node (ref "LEDS") (pin "4") (pinfunction "4_4") (pintype "passive"))
    )
    (net (code "47") (name "PC9") (class "Default")
      (node (ref "EXTRA") (pin "2") (pinfunction "2_2") (pintype "passive"))
      (node (ref "IC2") (pin "31") (pinfunction "PC9_31") (pintype "bidirectional"))
    )
    (net (code "48") (name "PE10") (class "Default")
      (node (ref "IC2") (pin "45") (pinfunction "PE10_45") (pintype "bidirectional"))
      (node (ref "RFID/SPI") (pin "1") (pinfunction "1_1") (pintype "passive"))
    )
    (net (code "49") (name "PE11") (class "Default")
      (node (ref "IC2") (pin "46") (pinfunction "PE11_46") (pintype "bidirectional"))
      (node (ref "RFID/SPI") (pin "2") (pinfunction "2_2") (pintype "passive"))
    )
    (net (code "50") (name "PE12") (class "Default")
      (node (ref "IC2") (pin "47") (pinfunction "PE12_47") (pintype "bidirectional"))
      (node (ref "RFID/SPI") (pin "3") (pinfunction "3_3") (pintype "passive"))
    )
    (net (code "51") (name "PE13") (class "Default")
      (node (ref "EXTRA") (pin "5") (pinfunction "5_5") (pintype "passive"))
      (node (ref "IC2") (pin "48") (pinfunction "PE13_48") (pintype "bidirectional"))
    )
    (net (code "52") (name "PF0") (class "Default")
      (node (ref "DBG_OPT") (pin "1") (pinfunction "1_1") (pintype "passive"))
      (node (ref "PF0") (pin "1") (pinfunction "1_1") (pintype "passive"))
    )
    (net (code "53") (name "PF1") (class "Default")
      (node (ref "DBG_OPT") (pin "2") (pinfunction "2_2") (pintype "passive"))
      (node (ref "PF1") (pin "1") (pinfunction "1_1") (pintype "passive"))
    )
    (net (code "54") (name "PF2") (class "Default")
      (node (ref "IC2") (pin "39") (pinfunction "PF2_39") (pintype "bidirectional"))
      (node (ref "TX") (pin "2") (pinfunction "2_2") (pintype "passive"))
      (node (ref "TX/RX_OPT") (pin "1") (pinfunction "1_1") (pintype "passive"))
    )
    (net (code "55") (name "PF3") (class "Default")
      (node (ref "EXTRA") (pin "3") (pinfunction "3_3") (pintype "passive"))
      (node (ref "IC2") (pin "40") (pinfunction "PF3_40") (pintype "bidirectional"))
    )
    (net (code "56") (name "PF5") (class "Default")
      (node (ref "EXTRA") (pin "4") (pinfunction "4_4") (pintype "passive"))
      (node (ref "IC2") (pin "42") (pinfunction "PF5_42") (pintype "bidirectional"))
    )
    (net (code "57") (name "SCL") (class "Default")
      (node (ref "7SEG/I2C") (pin "1") (pinfunction "1_1") (pintype "passive"))
      (node (ref "IC2") (pin "7") (pinfunction "PC1_7") (pintype "bidirectional"))
      (node (ref "IMU_I2C") (pin "1") (pinfunction "1_1") (pintype "passive"))
      (node (ref "R7") (pin "1") (pinfunction "1_1") (pintype "passive"))
      (node (ref "R9") (pin "1") (pinfunction "1_1") (pintype "passive"))
      (node (ref "SCL") (pin "2") (pinfunction "2_2") (pintype "passive"))
      (node (ref "TP8") (pin "TP") (pinfunction "TP_TP") (pintype "input"))
    )
    (net (code "58") (name "SCL{slash}SCLK") (class "Default")
      (node (ref "Q6") (pin "2") (pinfunction "S_2") (pintype "bidirectional"))
      (node (ref "R18") (pin "1") (pinfunction "1_1") (pintype "passive"))
      (node (ref "TP13") (pin "TP") (pinfunction "TP_TP") (pintype "input"))
      (node (ref "U3") (pin "23") (pinfunction "SCL/SCLK_23") (pintype "bidirectional"))
    )
    (net (code "59") (name "SCL{slash}SCLK_VIN") (class "Default")
      (node (ref "Q6") (pin "3") (pinfunction "D_3") (pintype "bidirectional"))
      (node (ref "R19") (pin "1") (pinfunction "1_1") (pintype "passive"))
      (node (ref "SCL") (pin "1") (pinfunction "1_1") (pintype "passive"))
    )
    (net (code "60") (name "SDA") (class "Default")
      (node (ref "7SEG/I2C") (pin "2") (pinfunction "2_2") (pintype "passive"))
      (node (ref "IC2") (pin "6") (pinfunction "PC0_6") (pintype "bidirectional"))
      (node (ref "IMU_I2C") (pin "2") (pinfunction "2_2") (pintype "passive"))
      (node (ref "R10") (pin "1") (pinfunction "1_1") (pintype "passive"))
      (node (ref "R8") (pin "1") (pinfunction "1_1") (pintype "passive"))
      (node (ref "SDA") (pin "2") (pinfunction "2_2") (pintype "passive"))
      (node (ref "TP7") (pin "TP") (pinfunction "TP_TP") (pintype "input"))
    )
    (net (code "61") (name "SDA{slash}SDI") (class "Default")
      (node (ref "Q8") (pin "2") (pinfunction "S_2") (pintype "bidirectional"))
      (node (ref "R20") (pin "1") (pinfunction "1_1") (pintype "passive"))
      (node (ref "TP14") (pin "TP") (pinfunction "TP_TP") (pintype "input"))
      (node (ref "U3") (pin "24") (pinfunction "SDA/SDI_24") (pintype "bidirectional"))
    )
    (net (code "62") (name "SDA{slash}SDI_VIN") (class "Default")
      (node (ref "Q8") (pin "3") (pinfunction "D_3") (pintype "bidirectional"))
      (node (ref "R21") (pin "1") (pinfunction "1_1") (pintype "passive"))
      (node (ref "SDA") (pin "1") (pinfunction "1_1") (pintype "passive"))
    )
    (net (code "63") (name "SENSOR_EN") (class "Default")
      (node (ref "IC2") (pin "14") (pinfunction "PA9_14") (pintype "bidirectional"))
      (node (ref "LORA") (pin "2") (pinfunction "2_2") (pintype "passive"))
    )
    (net (code "64") (name "SOLAR_VOLTAGE") (class "Default")
      (node (ref "R5") (pin "2") (pinfunction "2_2") (pintype "passive"))
      (node (ref "R6") (pin "1") (pinfunction "1_1") (pintype "passive"))
      (node (ref "SOLAR_V") (pin "1") (pinfunction "1_1") (pintype "passive"))
      (node (ref "TP1") (pin "TP") (pinfunction "TP_TP") (pintype "input"))
    )
    (net (code "65") (name "VDD") (class "Default")
      (node (ref "C25") (pin "1") (pinfunction "P$1_1") (pintype "passive"))
      (node (ref "C26") (pin "1") (pinfunction "P$1_1") (pintype "passive"))
      (node (ref "C27") (pin "1") (pinfunction "P$1_1") (pintype "passive"))
      (node (ref "C28") (pin "1") (pinfunction "P$1_1") (pintype "passive"))
      (node (ref "C29") (pin "1") (pinfunction "P$1_1") (pintype "passive"))
      (node (ref "DEBUG") (pin "1") (pinfunction "1_1") (pintype "passive"))
      (node (ref "FB1") (pin "1") (pinfunction "1_1") (pintype "bidirectional"))
      (node (ref "IC2") (pin "22") (pinfunction "IOVDD_3_22") (pintype "bidirectional"))
      (node (ref "IC2") (pin "28") (pinfunction "VDD_DREG_28") (pintype "bidirectional"))
      (node (ref "IC2") (pin "4") (pinfunction "IOVDD_0_4") (pintype "bidirectional"))
      (node (ref "IC2") (pin "43") (pinfunction "IOVDD_5_43") (pintype "bidirectional"))
      (node (ref "LORA_VDD") (pin "1") (pinfunction "1_1") (pintype "passive"))
      (node (ref "PWR") (pin "1") (pinfunction "1_1") (pintype "passive"))
      (node (ref "R10") (pin "2") (pinfunction "2_2") (pintype "passive"))
      (node (ref "R19") (pin "2") (pinfunction "2_2") (pintype "passive"))
      (node (ref "R21") (pin "2") (pinfunction "2_2") (pintype "passive"))
      (node (ref "R23") (pin "2") (pinfunction "2_2") (pintype "passive"))
      (node (ref "R32") (pin "2") (pinfunction "2_2") (pintype "passive"))
      (node (ref "R4") (pin "2") (pinfunction "2_2") (pintype "passive"))
      (node (ref "R7") (pin "2") (pinfunction "2_2") (pintype "passive"))
      (node (ref "R8") (pin "2") (pinfunction "2_2") (pintype "passive"))
      (node (ref "R9") (pin "2") (pinfunction "2_2") (pintype "passive"))
    )
    (net (code "66") (name "VDD_LORA") (class "Default")
      (node (ref "C2") (pin "1") (pinfunction "1_1") (pintype "passive"))
      (node (ref "C3") (pin "1") (pinfunction "1_1") (pintype "passive"))
      (node (ref "C6") (pin "1") (pinfunction "1_1") (pintype "passive"))
      (node (ref "C7") (pin "1") (pinfunction "1_1") (pintype "passive"))
      (node (ref "LORA_VDD") (pin "2") (pinfunction "2_2") (pintype "passive"))
      (node (ref "U$4") (pin "VDD") (pinfunction "VDD_VDD") (pintype "bidirectional"))
      (node (ref "U$4") (pin "VDD2") (pinfunction "VDD_VDD2") (pintype "bidirectional"))
    )
    (net (code "67") (name "V_BATT") (class "Default")
      (node (ref "ANALOG") (pin "2") (pinfunction "2_2") (pintype "passive"))
      (node (ref "R39") (pin "2") (pinfunction "2_2") (pintype "passive"))
    )
    (net (code "68") (name "V_SOLAR") (class "Default")
      (node (ref "ANALOG") (pin "1") (pinfunction "1_1") (pintype "passive"))
      (node (ref "R6") (pin "2") (pinfunction "2_2") (pintype "passive"))
    )
    (net (code "69") (name "unconnected-(EXTRA-Pad1)") (class "Default")
      (node (ref "EXTRA") (pin "1") (pinfunction "1_1") (pintype "passive"))
    )
    (net (code "70") (name "unconnected-(IC2-PC14-Pad35)") (class "Default")
      (node (ref "IC2") (pin "35") (pinfunction "PC14_35") (pintype "bidirectional"))
    )
    (net (code "71") (name "unconnected-(IC2-PC15-Pad36)") (class "Default")
      (node (ref "IC2") (pin "36") (pinfunction "PC15_36") (pintype "bidirectional"))
    )
    (net (code "72") (name "unconnected-(IC2-USB_VREGI-Pad33)") (class "Default")
      (node (ref "IC2") (pin "33") (pinfunction "USB_VREGI_33") (pintype "bidirectional"))
    )
    (net (code "73") (name "unconnected-(IC2-USB_VREGO-Pad34)") (class "Default")
      (node (ref "IC2") (pin "34") (pinfunction "USB_VREGO_34") (pintype "bidirectional"))
    )
    (net (code "74") (name "unconnected-(U$4-PadGPIO0)") (class "Default")
      (node (ref "U$4") (pin "GPIO0") (pinfunction "GPIO0_GPIO0") (pintype "bidirectional"))
    )
    (net (code "75") (name "unconnected-(U$4-PadGPIO1)") (class "Default")
      (node (ref "U$4") (pin "GPIO1") (pinfunction "GPIO1_GPIO1") (pintype "bidirectional"))
    )
    (net (code "76") (name "unconnected-(U$4-PadGPIO2)") (class "Default")
      (node (ref "U$4") (pin "GPIO2") (pinfunction "GPIO2_GPIO2") (pintype "bidirectional"))
    )
    (net (code "77") (name "unconnected-(U$4-PadGPIO3)") (class "Default")
      (node (ref "U$4") (pin "GPIO3") (pinfunction "GPIO3_GPIO3") (pintype "bidirectional"))
    )
    (net (code "78") (name "unconnected-(U$4-PadGPIO4)") (class "Default")
      (node (ref "U$4") (pin "GPIO4") (pinfunction "GPIO4_GPIO4") (pintype "bidirectional"))
    )
    (net (code "79") (name "unconnected-(U$4-PadGPIO5)") (class "Default")
      (node (ref "U$4") (pin "GPIO5") (pinfunction "GPIO5_GPIO5") (pintype "bidirectional"))
    )
    (net (code "80") (name "unconnected-(U$4-PadGPIO6)") (class "Default")
      (node (ref "U$4") (pin "GPIO6") (pinfunction "GPIO6_GPIO6") (pintype "bidirectional"))
    )
    (net (code "81") (name "unconnected-(U$4-PadGPIO7)") (class "Default")
      (node (ref "U$4") (pin "GPIO7") (pinfunction "GPIO7_GPIO7") (pintype "bidirectional"))
    )
    (net (code "82") (name "unconnected-(U$4-PadGPIO8)") (class "Default")
      (node (ref "U$4") (pin "GPIO8") (pinfunction "GPIO8_GPIO8") (pintype "bidirectional"))
    )
    (net (code "83") (name "unconnected-(U$4-PadGPIO9)") (class "Default")
      (node (ref "U$4") (pin "GPIO9") (pinfunction "GPIO9_GPIO9") (pintype "bidirectional"))
    )
    (net (code "84") (name "unconnected-(U$4-PadGPIO10)") (class "Default")
      (node (ref "U$4") (pin "GPIO10") (pinfunction "GPIO10_GPIO10") (pintype "bidirectional"))
    )
    (net (code "85") (name "unconnected-(U$4-PadGPIO11)") (class "Default")
      (node (ref "U$4") (pin "GPIO11") (pinfunction "GPIO11_GPIO11") (pintype "bidirectional"))
    )
    (net (code "86") (name "unconnected-(U$4-PadGPIO12)") (class "Default")
      (node (ref "U$4") (pin "GPIO12") (pinfunction "GPIO12_GPIO12") (pintype "bidirectional"))
    )
    (net (code "87") (name "unconnected-(U$4-PadGPIO13)") (class "Default")
      (node (ref "U$4") (pin "GPIO13") (pinfunction "GPIO13_GPIO13") (pintype "bidirectional"))
    )
    (net (code "88") (name "unconnected-(U$4-PadRFL)") (class "Default")
      (node (ref "U$4") (pin "RFL") (pinfunction "RFL_RFL") (pintype "bidirectional"))
    )
    (net (code "89") (name "unconnected-(U$4-PadUART_CTS)") (class "Default")
      (node (ref "U$4") (pin "UART_CTS") (pinfunction "UART_CTS_UART_CTS") (pintype "bidirectional"))
    )
    (net (code "90") (name "unconnected-(U$4-PadUART_RTS)") (class "Default")
      (node (ref "U$4") (pin "UART_RTS") (pinfunction "UART_RTS_UART_RTS") (pintype "bidirectional"))
    )
    (net (code "91") (name "unconnected-(U3-FSYNC-Pad11)") (class "Default")
      (node (ref "U3") (pin "11") (pinfunction "FSYNC_11") (pintype "bidirectional"))
    )
  )
)
